# urbanNoiseMonitor.net
KiCad netlist of a schematic drawn in EAGLE
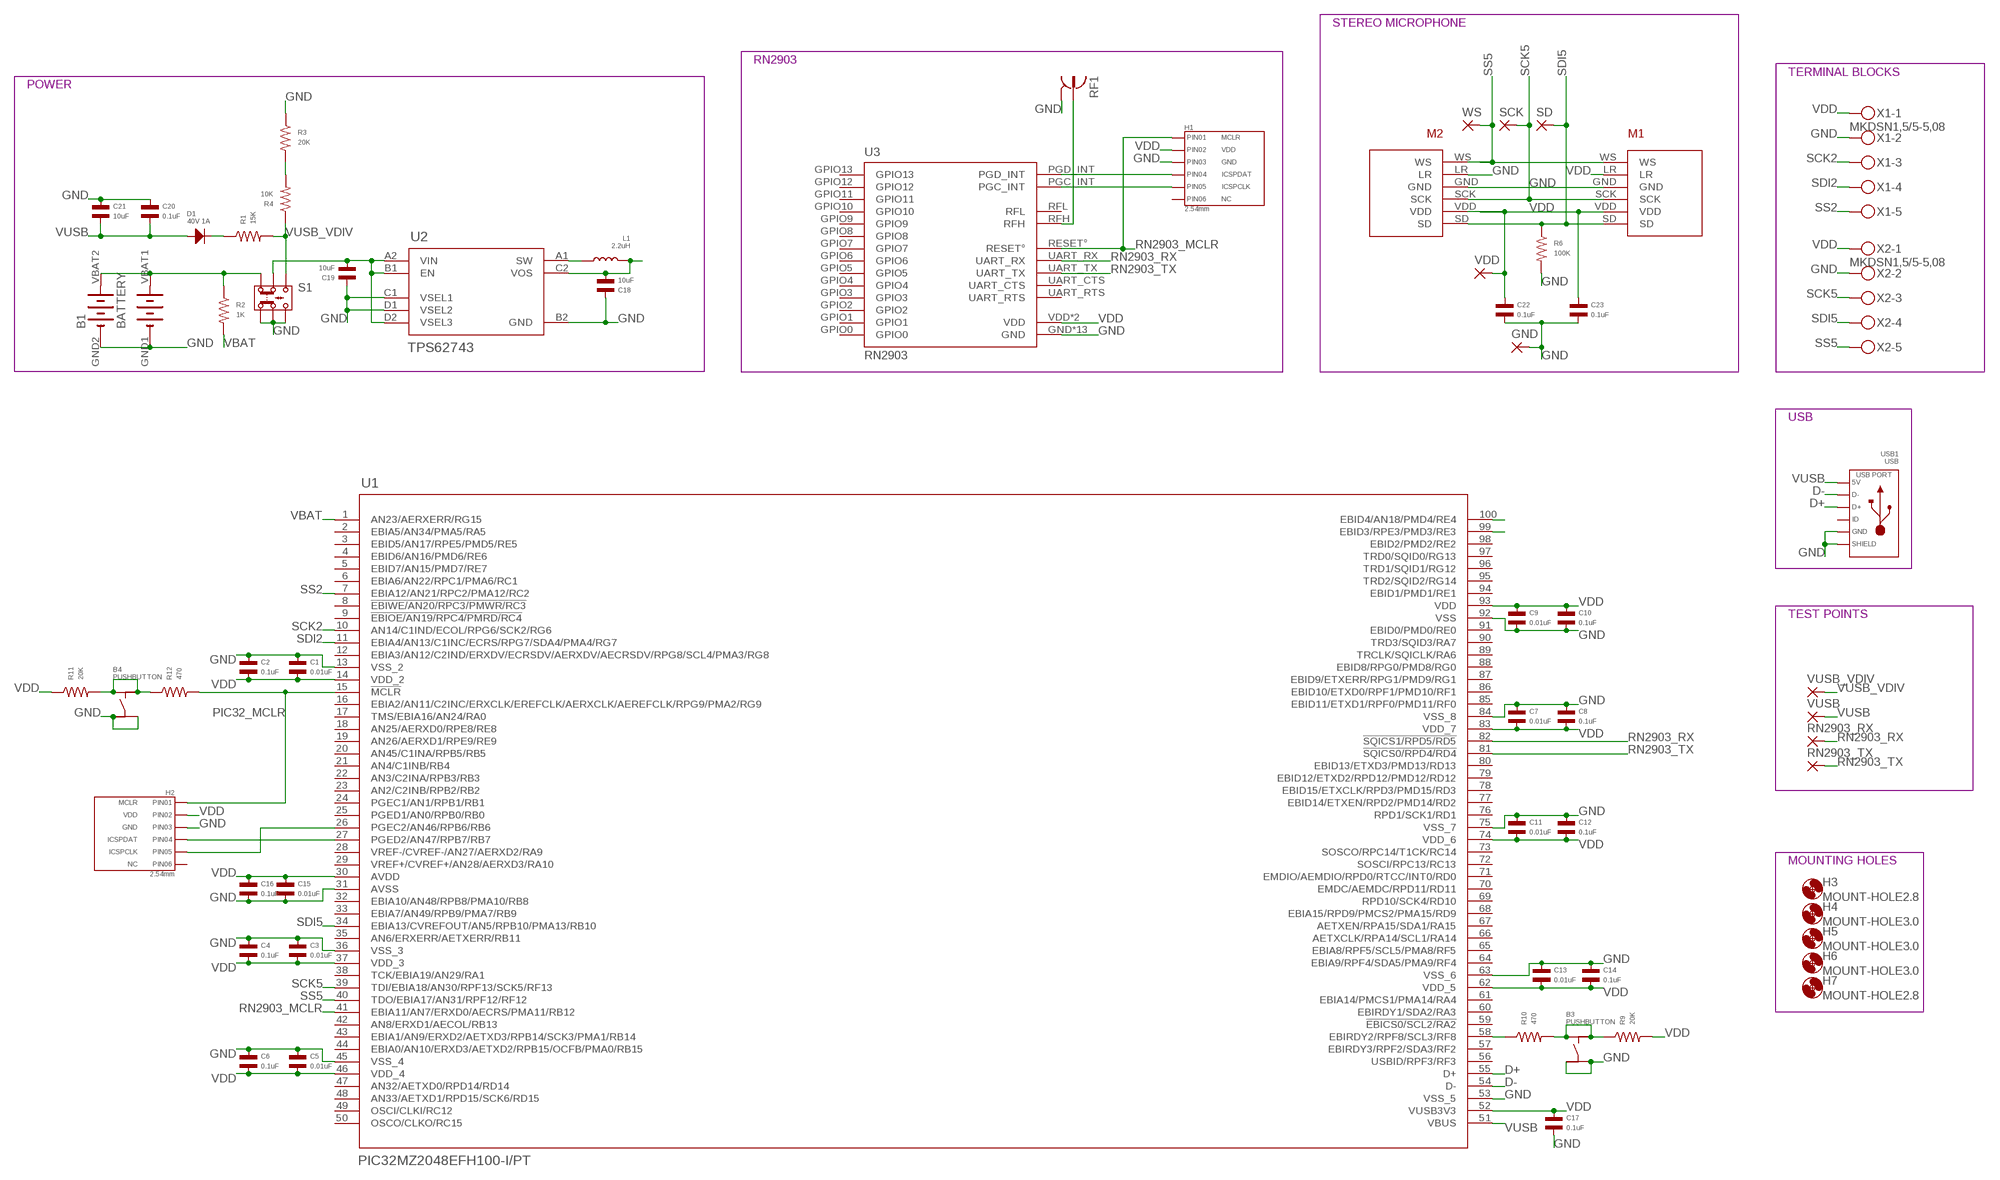
[diagram p0: schematic, sheet 1]

(export (version "E")
  (design (tool "Eeschema 10.0.6"))
  (components
    (comp (ref "B1")
      (value "BATTERY")
      (footprint "eagle-import:36-2227-ND")
      (fields (field (name "MPN") "36-2227-ND"))
      (libsource (lib "eagle-import") (part "BATTERY"))
    )
    (comp (ref "B3")
      (value "PUSHBUTTON")
      (footprint "eagle-import:TACT6MM")
      (fields (field (name "MPN") "MF-SW-TACT-6MM"))
      (libsource (lib "eagle-import") (part "PUSHBUTTON"))
    )
    (comp (ref "B4")
      (value "PUSHBUTTON")
      (footprint "eagle-import:TACT6MM")
      (fields (field (name "MPN") "MF-SW-TACT-6MM"))
      (libsource (lib "eagle-import") (part "PUSHBUTTON"))
    )
    (comp (ref "C1")
      (value "0.01uF")
      (footprint "eagle-import:C0402")
      (fields (field (name "MPN") "MF-CAP-0402-0.01uF"))
      (libsource (lib "eagle-import") (part "CAPACITOR_NP"))
    )
    (comp (ref "C2")
      (value "0.1uF")
      (footprint "eagle-import:C0402")
      (fields (field (name "MPN") "MF-CAP-0402-0.1uF"))
      (libsource (lib "eagle-import") (part "CAPACITOR_NP"))
    )
    (comp (ref "C3")
      (value "0.01uF")
      (footprint "eagle-import:C0402")
      (fields (field (name "MPN") "MF-CAP-0402-0.01uF"))
      (libsource (lib "eagle-import") (part "CAPACITOR_NP"))
    )
    (comp (ref "C4")
      (value "0.1uF")
      (footprint "eagle-import:C0402")
      (fields (field (name "MPN") "MF-CAP-0402-0.1uF"))
      (libsource (lib "eagle-import") (part "CAPACITOR_NP"))
    )
    (comp (ref "C5")
      (value "0.01uF")
      (footprint "eagle-import:C0402")
      (fields (field (name "MPN") "MF-CAP-0402-0.01uF"))
      (libsource (lib "eagle-import") (part "CAPACITOR_NP"))
    )
    (comp (ref "C6")
      (value "0.1uF")
      (footprint "eagle-import:C0402")
      (fields (field (name "MPN") "MF-CAP-0402-0.1uF"))
      (libsource (lib "eagle-import") (part "CAPACITOR_NP"))
    )
    (comp (ref "C7")
      (value "0.01uF")
      (footprint "eagle-import:C0402")
      (fields (field (name "MPN") "MF-CAP-0402-0.01uF"))
      (libsource (lib "eagle-import") (part "CAPACITOR_NP"))
    )
    (comp (ref "C8")
      (value "0.1uF")
      (footprint "eagle-import:C0402")
      (fields (field (name "MPN") "MF-CAP-0402-0.1uF"))
      (libsource (lib "eagle-import") (part "CAPACITOR_NP"))
    )
    (comp (ref "C9")
      (value "0.01uF")
      (footprint "eagle-import:C0402")
      (fields (field (name "MPN") "MF-CAP-0402-0.01uF"))
      (libsource (lib "eagle-import") (part "CAPACITOR_NP"))
    )
    (comp (ref "C10")
      (value "0.1uF")
      (footprint "eagle-import:C0402")
      (fields (field (name "MPN") "MF-CAP-0402-0.1uF"))
      (libsource (lib "eagle-import") (part "CAPACITOR_NP"))
    )
    (comp (ref "C11")
      (value "0.01uF")
      (footprint "eagle-import:C0402")
      (fields (field (name "MPN") "MF-CAP-0402-0.01uF"))
      (libsource (lib "eagle-import") (part "CAPACITOR_NP"))
    )
    (comp (ref "C12")
      (value "0.1uF")
      (footprint "eagle-import:C0402")
      (fields (field (name "MPN") "MF-CAP-0402-0.1uF"))
      (libsource (lib "eagle-import") (part "CAPACITOR_NP"))
    )
    (comp (ref "C13")
      (value "0.01uF")
      (footprint "eagle-import:C0402")
      (fields (field (name "MPN") "MF-CAP-0402-0.01uF"))
      (libsource (lib "eagle-import") (part "CAPACITOR_NP"))
    )
    (comp (ref "C14")
      (value "0.1uF")
      (footprint "eagle-import:C0402")
      (fields (field (name "MPN") "MF-CAP-0402-0.1uF"))
      (libsource (lib "eagle-import") (part "CAPACITOR_NP"))
    )
    (comp (ref "C15")
      (value "0.01uF")
      (footprint "eagle-import:C0402")
      (fields (field (name "MPN") "MF-CAP-0402-0.01uF"))
      (libsource (lib "eagle-import") (part "CAPACITOR_NP"))
    )
    (comp (ref "C16")
      (value "0.1uF")
      (footprint "eagle-import:C0402")
      (fields (field (name "MPN") "MF-CAP-0402-0.1uF"))
      (libsource (lib "eagle-import") (part "CAPACITOR_NP"))
    )
    (comp (ref "C17")
      (value "0.1uF")
      (footprint "eagle-import:C0402")
      (fields (field (name "MPN") "MF-CAP-0402-0.1uF"))
      (libsource (lib "eagle-import") (part "CAPACITOR_NP"))
    )
    (comp (ref "C18")
      (value "10uF")
      (footprint "eagle-import:C1206")
      (fields (field (name "MPN") "MF-CAP-1206-10uF"))
      (libsource (lib "eagle-import") (part "CAPACITOR_NPC1206"))
    )
    (comp (ref "C19")
      (value "10uF")
      (footprint "eagle-import:C1206")
      (fields (field (name "MPN") "MF-CAP-1206-10uF"))
      (libsource (lib "eagle-import") (part "CAPACITOR_NPC1206"))
    )
    (comp (ref "C20")
      (value "0.1uF")
      (footprint "eagle-import:C0402")
      (fields (field (name "MPN") "MF-CAP-0402-0.1uF"))
      (libsource (lib "eagle-import") (part "CAPACITOR_NP"))
    )
    (comp (ref "C21")
      (value "10uF")
      (footprint "eagle-import:C1206")
      (fields (field (name "MPN") "MF-CAP-1206-10uF"))
      (libsource (lib "eagle-import") (part "CAPACITOR_NPC1206"))
    )
    (comp (ref "C22")
      (value "0.1uF")
      (footprint "eagle-import:C0402")
      (fields (field (name "MPN") "MF-CAP-0402-0.1uF"))
      (libsource (lib "eagle-import") (part "CAPACITOR_NP"))
    )
    (comp (ref "C23")
      (value "0.1uF")
      (footprint "eagle-import:C0402")
      (fields (field (name "MPN") "MF-CAP-0402-0.1uF"))
      (libsource (lib "eagle-import") (part "CAPACITOR_NP"))
    )
    (comp (ref "D1")
      (value "40V 1A")
      (footprint "eagle-import:SMA")
      (fields (field (name "MPN") "MF-DIO-SMA-B140"))
      (libsource (lib "eagle-import") (part "SCHOTTKY_DIODE"))
    )
    (comp (ref "GND")
      (value "2,54/1,0")
      (footprint "eagle-import:2,54_1,0")
      (libsource (lib "eagle-import") (part "2,54/1,0"))
    )
    (comp (ref "H1")
      (value "2.54mm")
      (footprint "eagle-import:PTH_2.54MM_01X06")
      (fields
        (field (name "MPN") "MF-CON-2.54mm-01x06")
        (field (name "LABEL01") "MCLR")
        (field (name "LABEL02") "VDD")
        (field (name "LABEL03") "GND")
        (field (name "LABEL04") "ICSPDAT")
        (field (name "LABEL05") "ICSPCLK")
        (field (name "LABEL06") "NC")
        (field (name "POPULATE") "0")
      )
      (libsource (lib "eagle-import") (part "HEADER_PINS"))
    )
    (comp (ref "H2")
      (value "2.54mm")
      (footprint "eagle-import:PTH_2.54MM_01X06")
      (fields
        (field (name "MPN") "MF-CON-2.54mm-01x06")
        (field (name "LABEL01") "MCLR")
        (field (name "LABEL02") "VDD")
        (field (name "LABEL03") "GND")
        (field (name "LABEL04") "ICSPDAT")
        (field (name "LABEL05") "ICSPCLK")
        (field (name "LABEL06") "NC")
        (field (name "POPULATE") "0")
      )
      (libsource (lib "eagle-import") (part "HEADER_PINS"))
    )
    (comp (ref "H3")
      (value "MOUNT-HOLE2.8")
      (footprint "eagle-import:2,8")
      (libsource (lib "eagle-import") (part "MOUNT-HOLE2.8"))
    )
    (comp (ref "H4")
      (value "MOUNT-HOLE3.0")
      (footprint "eagle-import:3,0")
      (libsource (lib "eagle-import") (part "MOUNT-HOLE3.0"))
    )
    (comp (ref "H5")
      (value "MOUNT-HOLE3.0")
      (footprint "eagle-import:3,0")
      (libsource (lib "eagle-import") (part "MOUNT-HOLE3.0"))
    )
    (comp (ref "H6")
      (value "MOUNT-HOLE3.0")
      (footprint "eagle-import:3,0")
      (libsource (lib "eagle-import") (part "MOUNT-HOLE3.0"))
    )
    (comp (ref "H7")
      (value "MOUNT-HOLE2.8")
      (footprint "eagle-import:2,8")
      (libsource (lib "eagle-import") (part "MOUNT-HOLE2.8"))
    )
    (comp (ref "L1")
      (value "2.2uH")
      (footprint "eagle-import:L2016")
      (fields (field (name "MPN") "1285AS-H-2R2M=P2"))
      (libsource (lib "eagle-import") (part "DFE201610C"))
    )
    (comp (ref "M1")
      (value "MICROPHONE")
      (footprint "eagle-import:ICS-43434")
      (fields (field (name "MPN") "ICS-43434"))
      (libsource (lib "eagle-import") (part "MICROPHONE"))
    )
    (comp (ref "M2")
      (value "MICROPHONE")
      (footprint "eagle-import:ICS-43434")
      (fields (field (name "MPN") "ICS-43434"))
      (libsource (lib "eagle-import") (part "MICROPHONE"))
    )
    (comp (ref "R1")
      (value "15K")
      (footprint "eagle-import:R0402")
      (fields (field (name "MPN") "MF-RES-0402-15K"))
      (libsource (lib "eagle-import") (part "RESISTOR"))
    )
    (comp (ref "R2")
      (value "1K")
      (footprint "eagle-import:R0402")
      (fields (field (name "MPN") "MF-RES-0402-1K"))
      (libsource (lib "eagle-import") (part "RESISTOR"))
    )
    (comp (ref "R3")
      (value "20K")
      (footprint "eagle-import:R0805")
      (fields (field (name "MPN") "MF-RES-0805-20K"))
      (libsource (lib "eagle-import") (part "RESISTORR0805"))
    )
    (comp (ref "R4")
      (value "10K")
      (footprint "eagle-import:R0402")
      (fields (field (name "MPN") "MF-RES-0402-10K"))
      (libsource (lib "eagle-import") (part "RESISTOR"))
    )
    (comp (ref "R6")
      (value "100K")
      (footprint "eagle-import:R0402")
      (fields (field (name "MPN") "MF-RES-0402-100K"))
      (libsource (lib "eagle-import") (part "RESISTOR"))
    )
    (comp (ref "R9")
      (value "20K")
      (footprint "eagle-import:R0805")
      (fields (field (name "MPN") "MF-RES-0805-20K"))
      (libsource (lib "eagle-import") (part "RESISTORR0805"))
    )
    (comp (ref "R10")
      (value "470")
      (footprint "eagle-import:R0402")
      (fields (field (name "MPN") "MF-RES-0402-470"))
      (libsource (lib "eagle-import") (part "RESISTOR"))
    )
    (comp (ref "R11")
      (value "20K")
      (footprint "eagle-import:R0805")
      (fields (field (name "MPN") "MF-RES-0805-20K"))
      (libsource (lib "eagle-import") (part "RESISTORR0805"))
    )
    (comp (ref "R12")
      (value "470")
      (footprint "eagle-import:R0402")
      (fields (field (name "MPN") "MF-RES-0402-470"))
      (libsource (lib "eagle-import") (part "RESISTOR"))
    )
    (comp (ref "RF1")
      (value "SMA_JACK")
      (footprint "eagle-import:J502-ND-142-0711-821_826")
      (fields (field (name "MPN") "SMA-J-P-H-ST-EM1"))
      (libsource (lib "eagle-import") (part "SMA_JACK"))
    )
    (comp (ref "RN2903_RX")
      (value "2,54/1,0")
      (footprint "eagle-import:2,54_1,0")
      (libsource (lib "eagle-import") (part "2,54/1,0"))
    )
    (comp (ref "RN2903_TX")
      (value "2,54/1,0")
      (footprint "eagle-import:2,54_1,0")
      (libsource (lib "eagle-import") (part "2,54/1,0"))
    )
    (comp (ref "S1")
      (value "SLIDING_SWITCH")
      (footprint "eagle-import:DPDT")
      (fields (field (name "MPN") "JS202011SCQN"))
      (libsource (lib "eagle-import") (part "SLIDING_SWITCH"))
    )
    (comp (ref "SCK")
      (value "2,54/1,0")
      (footprint "eagle-import:2,54_1,0")
      (libsource (lib "eagle-import") (part "2,54/1,0"))
    )
    (comp (ref "SD")
      (value "2,54/1,0")
      (footprint "eagle-import:2,54_1,0")
      (libsource (lib "eagle-import") (part "2,54/1,0"))
    )
    (comp (ref "U1")
      (value "PIC32MZ2048EFH100-I/PT")
      (footprint "eagle-import:TQFP100_12X12MC")
      (libsource (lib "eagle-import") (part "PIC32MZ2048EFH100-I/PT"))
    )
    (comp (ref "U2")
      (value "TPS62743")
      (footprint "eagle-import:YFP0008AGAC")
      (fields (field (name "MPN") "TPS62743YFPR"))
      (libsource (lib "eagle-import") (part "TPS62743"))
    )
    (comp (ref "U3")
      (value "RN2903")
      (footprint "eagle-import:RN2903")
      (fields (field (name "MPN") "RN2903A-I/RM098"))
      (libsource (lib "eagle-import") (part "RN2903"))
    )
    (comp (ref "USB1")
      (value "USB")
      (footprint "eagle-import:MICROUSB-RIGHT")
      (fields (field (name "MPN") "MF-CON-MICROUSB-RIGHT"))
      (libsource (lib "eagle-import") (part "USB"))
    )
    (comp (ref "VDD")
      (value "2,54/1,0")
      (footprint "eagle-import:2,54_1,0")
      (libsource (lib "eagle-import") (part "2,54/1,0"))
    )
    (comp (ref "VUSB")
      (value "2,54/1,0")
      (footprint "eagle-import:2,54_1,0")
      (libsource (lib "eagle-import") (part "2,54/1,0"))
    )
    (comp (ref "VUSB_VDIV")
      (value "2,54/1,0")
      (footprint "eagle-import:2,54_1,0")
      (libsource (lib "eagle-import") (part "2,54/1,0"))
    )
    (comp (ref "WS")
      (value "2,54/1,0")
      (footprint "eagle-import:2,54_1,0")
      (libsource (lib "eagle-import") (part "2,54/1,0"))
    )
    (comp (ref "X1")
      (value "MKDSN1,5/5-5,08")
      (footprint "eagle-import:MKDSN1,5_5-5,08")
      (fields (field (name "MPN") "1729157") (field (name "POPULATE") "0"))
      (libsource (lib "eagle-import") (part "MKDSN1,5/5-5,08"))
    )
    (comp (ref "X2")
      (value "MKDSN1,5/5-5,08")
      (footprint "eagle-import:MKDSN1,5_5-5,08")
      (fields (field (name "MPN") "1729157") (field (name "POPULATE") "0"))
      (libsource (lib "eagle-import") (part "MKDSN1,5/5-5,08"))
    )
  )
  (nets
    (net (code "1") (name "/D+") (class "Default")
      (node (ref "U1") (pin "55") (pinfunction "D+_55") (pintype "passive"))
      (node (ref "USB1") (pin "3") (pinfunction "D+_3") (pintype "bidirectional"))
    )
    (net (code "2") (name "/D-") (class "Default")
      (node (ref "U1") (pin "54") (pinfunction "D-_54") (pintype "passive"))
      (node (ref "USB1") (pin "2") (pinfunction "D-_2") (pintype "bidirectional"))
    )
    (net (code "3") (name "/GND") (class "Default")
      (node (ref "B1") (pin "GND1") (pinfunction "GND1_GND1") (pintype "passive"))
      (node (ref "B1") (pin "GND2") (pinfunction "GND2_GND2") (pintype "passive"))
      (node (ref "B3") (pin "P$3") (pinfunction "P$3_P$3") (pintype "bidirectional"))
      (node (ref "B3") (pin "P$4") (pinfunction "P$4_P$4") (pintype "bidirectional"))
      (node (ref "B4") (pin "P$3") (pinfunction "P$3_P$3") (pintype "bidirectional"))
      (node (ref "B4") (pin "P$4") (pinfunction "P$4_P$4") (pintype "bidirectional"))
      (node (ref "C1") (pin "P$1") (pinfunction "P$1_P$1") (pintype "passive"))
      (node (ref "C10") (pin "P$2") (pinfunction "P$2_P$2") (pintype "passive"))
      (node (ref "C11") (pin "P$1") (pinfunction "P$1_P$1") (pintype "passive"))
      (node (ref "C12") (pin "P$1") (pinfunction "P$1_P$1") (pintype "passive"))
      (node (ref "C13") (pin "P$1") (pinfunction "P$1_P$1") (pintype "passive"))
      (node (ref "C14") (pin "P$1") (pinfunction "P$1_P$1") (pintype "passive"))
      (node (ref "C15") (pin "P$2") (pinfunction "P$2_P$2") (pintype "passive"))
      (node (ref "C16") (pin "P$2") (pinfunction "P$2_P$2") (pintype "passive"))
      (node (ref "C17") (pin "P$2") (pinfunction "P$2_P$2") (pintype "passive"))
      (node (ref "C18") (pin "P$1") (pinfunction "P$1_P$1") (pintype "passive"))
      (node (ref "C19") (pin "P$1") (pinfunction "P$1_P$1") (pintype "passive"))
      (node (ref "C2") (pin "P$1") (pinfunction "P$1_P$1") (pintype "passive"))
      (node (ref "C20") (pin "P$1") (pinfunction "P$1_P$1") (pintype "passive"))
      (node (ref "C21") (pin "P$1") (pinfunction "P$1_P$1") (pintype "passive"))
      (node (ref "C22") (pin "P$2") (pinfunction "P$2_P$2") (pintype "passive"))
      (node (ref "C23") (pin "P$2") (pinfunction "P$2_P$2") (pintype "passive"))
      (node (ref "C3") (pin "P$1") (pinfunction "P$1_P$1") (pintype "passive"))
      (node (ref "C4") (pin "P$1") (pinfunction "P$1_P$1") (pintype "passive"))
      (node (ref "C5") (pin "P$1") (pinfunction "P$1_P$1") (pintype "passive"))
      (node (ref "C6") (pin "P$1") (pinfunction "P$1_P$1") (pintype "passive"))
      (node (ref "C7") (pin "P$1") (pinfunction "P$1_P$1") (pintype "passive"))
      (node (ref "C8") (pin "P$1") (pinfunction "P$1_P$1") (pintype "passive"))
      (node (ref "C9") (pin "P$2") (pinfunction "P$2_P$2") (pintype "passive"))
      (node (ref "GND") (pin "1") (pinfunction "P_1") (pintype "passive"))
      (node (ref "H1") (pin "P$3") (pinfunction "PIN3_P$3") (pintype "bidirectional"))
      (node (ref "H2") (pin "P$3") (pinfunction "PIN3_P$3") (pintype "bidirectional"))
      (node (ref "M1") (pin "GND") (pinfunction "GND_GND") (pintype "bidirectional"))
      (node (ref "M2") (pin "GND") (pinfunction "GND_GND") (pintype "bidirectional"))
      (node (ref "M2") (pin "LR") (pinfunction "LR_LR") (pintype "bidirectional"))
      (node (ref "R3") (pin "P$1") (pinfunction "P$1_P$1") (pintype "passive"))
      (node (ref "R6") (pin "P$2") (pinfunction "P$2_P$2") (pintype "passive"))
      (node (ref "RF1") (pin "G@1") (pinfunction "2_G@1") (pintype "passive"))
      (node (ref "RF1") (pin "G@2") (pinfunction "2_G@2") (pintype "passive"))
      (node (ref "RF1") (pin "G@3") (pinfunction "2_G@3") (pintype "passive"))
      (node (ref "RF1") (pin "G@4") (pinfunction "2_G@4") (pintype "passive"))
      (node (ref "S1") (pin "1") (pinfunction "1_1") (pintype "passive"))
      (node (ref "S1") (pin "2") (pinfunction "2_2") (pintype "passive"))
      (node (ref "S1") (pin "3") (pinfunction "3_3") (pintype "passive"))
      (node (ref "U1") (pin "13") (pinfunction "VSS_2_13") (pintype "power_in"))
      (node (ref "U1") (pin "31") (pinfunction "AVSS_31") (pintype "power_in"))
      (node (ref "U1") (pin "36") (pinfunction "VSS_3_36") (pintype "power_in"))
      (node (ref "U1") (pin "45") (pinfunction "VSS_4_45") (pintype "power_in"))
      (node (ref "U1") (pin "53") (pinfunction "VSS_5_53") (pintype "power_in"))
      (node (ref "U1") (pin "63") (pinfunction "VSS_6_63") (pintype "power_in"))
      (node (ref "U1") (pin "75") (pinfunction "VSS_7_75") (pintype "power_in"))
      (node (ref "U1") (pin "84") (pinfunction "VSS_8_84") (pintype "power_in"))
      (node (ref "U1") (pin "92") (pinfunction "VSS_92") (pintype "power_in"))
      (node (ref "U2") (pin "B2") (pinfunction "GND_B2") (pintype "power_in"))
      (node (ref "U2") (pin "C1") (pinfunction "VSEL1_C1") (pintype "input"))
      (node (ref "U2") (pin "D1") (pinfunction "VSEL2_D1") (pintype "input"))
      (node (ref "U3") (pin "GND") (pinfunction "GND_GND") (pintype "bidirectional"))
      (node (ref "U3") (pin "GND1") (pinfunction "GND_GND1") (pintype "bidirectional"))
      (node (ref "U3") (pin "GND10") (pinfunction "GND_GND10") (pintype "bidirectional"))
      (node (ref "U3") (pin "GND11") (pinfunction "GND_GND11") (pintype "bidirectional"))
      (node (ref "U3") (pin "GND12") (pinfunction "GND_GND12") (pintype "bidirectional"))
      (node (ref "U3") (pin "GND2") (pinfunction "GND_GND2") (pintype "bidirectional"))
      (node (ref "U3") (pin "GND3") (pinfunction "GND_GND3") (pintype "bidirectional"))
      (node (ref "U3") (pin "GND4") (pinfunction "GND_GND4") (pintype "bidirectional"))
      (node (ref "U3") (pin "GND5") (pinfunction "GND_GND5") (pintype "bidirectional"))
      (node (ref "U3") (pin "GND6") (pinfunction "GND_GND6") (pintype "bidirectional"))
      (node (ref "U3") (pin "GND7") (pinfunction "GND_GND7") (pintype "bidirectional"))
      (node (ref "U3") (pin "GND8") (pinfunction "GND_GND8") (pintype "bidirectional"))
      (node (ref "U3") (pin "GND9") (pinfunction "GND_GND9") (pintype "bidirectional"))
      (node (ref "USB1") (pin "5") (pinfunction "GND_5") (pintype "power_in"))
      (node (ref "USB1") (pin "S1") (pinfunction "SLD_S1") (pintype "power_in"))
      (node (ref "USB1") (pin "S2") (pinfunction "SLD_S2") (pintype "power_in"))
      (node (ref "USB1") (pin "S3") (pinfunction "SLD_S3") (pintype "power_in"))
      (node (ref "USB1") (pin "S4") (pinfunction "SLD_S4") (pintype "power_in"))
      (node (ref "USB1") (pin "S5") (pinfunction "SLD_S5") (pintype "power_in"))
      (node (ref "USB1") (pin "S6") (pinfunction "SLD_S6") (pintype "power_in"))
      (node (ref "X1") (pin "2") (pinfunction "KL_2") (pintype "passive"))
      (node (ref "X2") (pin "2") (pinfunction "KL_2") (pintype "passive"))
    )
    (net (code "4") (name "/PIC32_MCLR") (class "Default")
      (node (ref "H2") (pin "P$1") (pinfunction "PIN1_P$1") (pintype "bidirectional"))
      (node (ref "R12") (pin "P$2") (pinfunction "P$2_P$2") (pintype "passive"))
      (node (ref "U1") (pin "15") (pinfunction "~{MCLR}_15") (pintype "passive"))
    )
    (net (code "5") (name "/RN2903_MCLR") (class "Default")
      (node (ref "H1") (pin "P$1") (pinfunction "PIN1_P$1") (pintype "bidirectional"))
      (node (ref "U1") (pin "41") (pinfunction "EBIA11/AN7/ERXD0/AECRS/PMA11/RB12_41") (pintype "bidirectional"))
      (node (ref "U3") (pin "RESET°") (pinfunction "RESET°_RESET°") (pintype "bidirectional"))
    )
    (net (code "6") (name "/RN2903_RX") (class "Default")
      (node (ref "RN2903_RX") (pin "1") (pinfunction "P_1") (pintype "passive"))
      (node (ref "U1") (pin "82") (pinfunction "~{SQICS1/RPD5/RD5}_82") (pintype "bidirectional"))
      (node (ref "U3") (pin "UART_RX") (pinfunction "UART_RX_UART_RX") (pintype "bidirectional"))
    )
    (net (code "7") (name "/RN2903_TX") (class "Default")
      (node (ref "RN2903_TX") (pin "1") (pinfunction "P_1") (pintype "passive"))
      (node (ref "U1") (pin "81") (pinfunction "~{SQICS0/RPD4/RD4}_81") (pintype "bidirectional"))
      (node (ref "U3") (pin "UART_TX") (pinfunction "UART_TX_UART_TX") (pintype "bidirectional"))
    )
    (net (code "8") (name "/SCK2") (class "Default")
      (node (ref "U1") (pin "10") (pinfunction "AN14/C1IND/ECOL/RPG6/SCK2/RG6_10") (pintype "bidirectional"))
      (node (ref "X1") (pin "3") (pinfunction "KL_3") (pintype "passive"))
    )
    (net (code "9") (name "/SCK5") (class "Default")
      (node (ref "M1") (pin "SCK") (pinfunction "SCK_SCK") (pintype "bidirectional"))
      (node (ref "M2") (pin "SCK") (pinfunction "SCK_SCK") (pintype "bidirectional"))
      (node (ref "SCK") (pin "1") (pinfunction "P_1") (pintype "passive"))
      (node (ref "U1") (pin "39") (pinfunction "TDI/EBIA18/AN30/RPF13/SCK5/RF13_39") (pintype "bidirectional"))
      (node (ref "X2") (pin "3") (pinfunction "KL_3") (pintype "passive"))
    )
    (net (code "10") (name "/SDI2") (class "Default")
      (node (ref "U1") (pin "11") (pinfunction "EBIA4/AN13/C1INC/ECRS/RPG7/SDA4/PMA4/RG7_11") (pintype "bidirectional"))
      (node (ref "X1") (pin "4") (pinfunction "KL_4") (pintype "passive"))
    )
    (net (code "11") (name "/SDI5") (class "Default")
      (node (ref "M1") (pin "SD") (pinfunction "SD_SD") (pintype "bidirectional"))
      (node (ref "M2") (pin "SD") (pinfunction "SD_SD") (pintype "bidirectional"))
      (node (ref "R6") (pin "P$1") (pinfunction "P$1_P$1") (pintype "passive"))
      (node (ref "SD") (pin "1") (pinfunction "P_1") (pintype "passive"))
      (node (ref "U1") (pin "34") (pinfunction "EBIA13/CVREFOUT/AN5/RPB10/PMA13/RB10_34") (pintype "bidirectional"))
      (node (ref "X2") (pin "4") (pinfunction "KL_4") (pintype "passive"))
    )
    (net (code "12") (name "/SS2") (class "Default")
      (node (ref "U1") (pin "7") (pinfunction "EBIA12/AN21/RPC2/PMA12/RC2_7") (pintype "bidirectional"))
      (node (ref "X1") (pin "5") (pinfunction "KL_5") (pintype "passive"))
    )
    (net (code "13") (name "/SS5") (class "Default")
      (node (ref "M1") (pin "WS") (pinfunction "WS_WS") (pintype "bidirectional"))
      (node (ref "M2") (pin "WS") (pinfunction "WS_WS") (pintype "bidirectional"))
      (node (ref "U1") (pin "40") (pinfunction "TDO/EBIA17/AN31/RPF12/RF12_40") (pintype "bidirectional"))
      (node (ref "WS") (pin "1") (pinfunction "P_1") (pintype "passive"))
      (node (ref "X2") (pin "5") (pinfunction "KL_5") (pintype "passive"))
    )
    (net (code "14") (name "/VBAT") (class "Default")
      (node (ref "R2") (pin "P$2") (pinfunction "P$2_P$2") (pintype "passive"))
      (node (ref "U1") (pin "1") (pinfunction "AN23/AERXERR/RG15_1") (pintype "bidirectional"))
    )
    (net (code "15") (name "/VDD") (class "Default")
      (node (ref "C1") (pin "P$2") (pinfunction "P$2_P$2") (pintype "passive"))
      (node (ref "C10") (pin "P$1") (pinfunction "P$1_P$1") (pintype "passive"))
      (node (ref "C11") (pin "P$2") (pinfunction "P$2_P$2") (pintype "passive"))
      (node (ref "C12") (pin "P$2") (pinfunction "P$2_P$2") (pintype "passive"))
      (node (ref "C13") (pin "P$2") (pinfunction "P$2_P$2") (pintype "passive"))
      (node (ref "C14") (pin "P$2") (pinfunction "P$2_P$2") (pintype "passive"))
      (node (ref "C15") (pin "P$1") (pinfunction "P$1_P$1") (pintype "passive"))
      (node (ref "C16") (pin "P$1") (pinfunction "P$1_P$1") (pintype "passive"))
      (node (ref "C17") (pin "P$1") (pinfunction "P$1_P$1") (pintype "passive"))
      (node (ref "C18") (pin "P$2") (pinfunction "P$2_P$2") (pintype "passive"))
      (node (ref "C2") (pin "P$2") (pinfunction "P$2_P$2") (pintype "passive"))
      (node (ref "C22") (pin "P$1") (pinfunction "P$1_P$1") (pintype "passive"))
      (node (ref "C23") (pin "P$1") (pinfunction "P$1_P$1") (pintype "passive"))
      (node (ref "C3") (pin "P$2") (pinfunction "P$2_P$2") (pintype "passive"))
      (node (ref "C4") (pin "P$2") (pinfunction "P$2_P$2") (pintype "passive"))
      (node (ref "C5") (pin "P$2") (pinfunction "P$2_P$2") (pintype "passive"))
      (node (ref "C6") (pin "P$2") (pinfunction "P$2_P$2") (pintype "passive"))
      (node (ref "C7") (pin "P$2") (pinfunction "P$2_P$2") (pintype "passive"))
      (node (ref "C8") (pin "P$2") (pinfunction "P$2_P$2") (pintype "passive"))
      (node (ref "C9") (pin "P$1") (pinfunction "P$1_P$1") (pintype "passive"))
      (node (ref "H1") (pin "P$2") (pinfunction "PIN2_P$2") (pintype "bidirectional"))
      (node (ref "H2") (pin "P$2") (pinfunction "PIN2_P$2") (pintype "bidirectional"))
      (node (ref "L1") (pin "P$1") (pinfunction "P$1_P$1") (pintype "passive"))
      (node (ref "M1") (pin "LR") (pinfunction "LR_LR") (pintype "bidirectional"))
      (node (ref "M1") (pin "VDD") (pinfunction "VDD_VDD") (pintype "bidirectional"))
      (node (ref "M2") (pin "VDD") (pinfunction "VDD_VDD") (pintype "bidirectional"))
      (node (ref "R11") (pin "P$1") (pinfunction "P$1_P$1") (pintype "passive"))
      (node (ref "R9") (pin "P$2") (pinfunction "P$2_P$2") (pintype "passive"))
      (node (ref "U1") (pin "14") (pinfunction "VDD_2_14") (pintype "power_in"))
      (node (ref "U1") (pin "30") (pinfunction "AVDD_30") (pintype "power_in"))
      (node (ref "U1") (pin "37") (pinfunction "VDD_3_37") (pintype "power_in"))
      (node (ref "U1") (pin "46") (pinfunction "VDD_4_46") (pintype "power_in"))
      (node (ref "U1") (pin "52") (pinfunction "VUSB3V3_52") (pintype "power_in"))
      (node (ref "U1") (pin "62") (pinfunction "VDD_5_62") (pintype "power_in"))
      (node (ref "U1") (pin "74") (pinfunction "VDD_6_74") (pintype "power_in"))
      (node (ref "U1") (pin "83") (pinfunction "VDD_7_83") (pintype "power_in"))
      (node (ref "U1") (pin "93") (pinfunction "VDD_93") (pintype "power_in"))
      (node (ref "U2") (pin "C2") (pinfunction "VOS_C2") (pintype "input"))
      (node (ref "U3") (pin "VDD") (pinfunction "VDD_VDD") (pintype "bidirectional"))
      (node (ref "U3") (pin "VDD2") (pinfunction "VDD_VDD2") (pintype "bidirectional"))
      (node (ref "VDD") (pin "1") (pinfunction "P_1") (pintype "passive"))
      (node (ref "X1") (pin "1") (pinfunction "KL_1") (pintype "passive"))
      (node (ref "X2") (pin "1") (pinfunction "KL_1") (pintype "passive"))
    )
    (net (code "16") (name "/VUSB") (class "Default")
      (node (ref "C20") (pin "P$2") (pinfunction "P$2_P$2") (pintype "passive"))
      (node (ref "C21") (pin "P$2") (pinfunction "P$2_P$2") (pintype "passive"))
      (node (ref "D1") (pin "ANODE") (pinfunction "ANODE_ANODE") (pintype "bidirectional"))
      (node (ref "U1") (pin "51") (pinfunction "VBUS_51") (pintype "power_in"))
      (node (ref "USB1") (pin "1") (pinfunction "5V_1") (pintype "power_in"))
      (node (ref "VUSB") (pin "1") (pinfunction "P_1") (pintype "passive"))
    )
    (net (code "17") (name "/VUSB_VDIV") (class "Default")
      (node (ref "R1") (pin "P$2") (pinfunction "P$2_P$2") (pintype "passive"))
      (node (ref "R4") (pin "P$1") (pinfunction "P$1_P$1") (pintype "passive"))
      (node (ref "S1") (pin "6") (pinfunction "6_6") (pintype "passive"))
      (node (ref "VUSB_VDIV") (pin "1") (pinfunction "P_1") (pintype "passive"))
    )
    (net (code "18") (name "Net-(B1-PadVBAT1)") (class "Default")
      (node (ref "B1") (pin "VBAT1") (pinfunction "VBAT1_VBAT1") (pintype "passive"))
      (node (ref "B1") (pin "VBAT2") (pinfunction "VBAT2_VBAT2") (pintype "passive"))
      (node (ref "R2") (pin "P$1") (pinfunction "P$1_P$1") (pintype "passive"))
      (node (ref "S1") (pin "4") (pinfunction "4_4") (pintype "passive"))
    )
    (net (code "19") (name "Net-(B3-PadP$1)") (class "Default")
      (node (ref "B3") (pin "P$1") (pinfunction "P$1_P$1") (pintype "bidirectional"))
      (node (ref "B3") (pin "P$2") (pinfunction "P$2_P$2") (pintype "bidirectional"))
      (node (ref "R10") (pin "P$2") (pinfunction "P$2_P$2") (pintype "passive"))
      (node (ref "R9") (pin "P$1") (pinfunction "P$1_P$1") (pintype "passive"))
    )
    (net (code "20") (name "Net-(B4-PadP$1)") (class "Default")
      (node (ref "B4") (pin "P$1") (pinfunction "P$1_P$1") (pintype "bidirectional"))
      (node (ref "B4") (pin "P$2") (pinfunction "P$2_P$2") (pintype "bidirectional"))
      (node (ref "R11") (pin "P$2") (pinfunction "P$2_P$2") (pintype "passive"))
      (node (ref "R12") (pin "P$1") (pinfunction "P$1_P$1") (pintype "passive"))
    )
    (net (code "21") (name "Net-(D1-PadCATHODE)") (class "Default")
      (node (ref "D1") (pin "CATHODE") (pinfunction "CATHODE_CATHODE") (pintype "bidirectional"))
      (node (ref "R1") (pin "P$1") (pinfunction "P$1_P$1") (pintype "passive"))
    )
    (net (code "22") (name "Net-(H1-PIN4)") (class "Default")
      (node (ref "H1") (pin "P$4") (pinfunction "PIN4_P$4") (pintype "bidirectional"))
      (node (ref "U3") (pin "PGD_INT") (pinfunction "PGD_INT_PGD_INT") (pintype "bidirectional"))
    )
    (net (code "23") (name "Net-(H1-PIN5)") (class "Default")
      (node (ref "H1") (pin "P$5") (pinfunction "PIN5_P$5") (pintype "bidirectional"))
      (node (ref "U3") (pin "PGC_INT") (pinfunction "PGC_INT_PGC_INT") (pintype "bidirectional"))
    )
    (net (code "24") (name "Net-(H2-PIN4)") (class "Default")
      (node (ref "H2") (pin "P$4") (pinfunction "PIN4_P$4") (pintype "bidirectional"))
      (node (ref "U1") (pin "27") (pinfunction "PGED2/AN47/RPB7/RB7_27") (pintype "bidirectional"))
    )
    (net (code "25") (name "Net-(H2-PIN5)") (class "Default")
      (node (ref "H2") (pin "P$5") (pinfunction "PIN5_P$5") (pintype "bidirectional"))
      (node (ref "U1") (pin "26") (pinfunction "PGEC2/AN46/RPB6/RB6_26") (pintype "bidirectional"))
    )
    (net (code "26") (name "Net-(R3-PadP$2)") (class "Default")
      (node (ref "R3") (pin "P$2") (pinfunction "P$2_P$2") (pintype "passive"))
      (node (ref "R4") (pin "P$2") (pinfunction "P$2_P$2") (pintype "passive"))
    )
    (net (code "27") (name "Net-(RF1-Pad1)") (class "Default")
      (node (ref "RF1") (pin "1") (pinfunction "1_1") (pintype "passive"))
      (node (ref "U3") (pin "RFH") (pinfunction "RFH_RFH") (pintype "bidirectional"))
    )
    (net (code "28") (name "Net-(U1-EBIRDY2{slash}RPF8{slash}SCL3{slash}RF8)") (class "Default")
      (node (ref "R10") (pin "P$1") (pinfunction "P$1_P$1") (pintype "passive"))
      (node (ref "U1") (pin "58") (pinfunction "EBIRDY2/RPF8/SCL3/RF8_58") (pintype "bidirectional"))
    )
    (net (code "29") (name "Net-(U2-EN)") (class "Default")
      (node (ref "C19") (pin "P$2") (pinfunction "P$2_P$2") (pintype "passive"))
      (node (ref "S1") (pin "5") (pinfunction "5_5") (pintype "passive"))
      (node (ref "U2") (pin "A2") (pinfunction "VIN_A2") (pintype "power_in"))
      (node (ref "U2") (pin "B1") (pinfunction "EN_B1") (pintype "input"))
      (node (ref "U2") (pin "D2") (pinfunction "VSEL3_D2") (pintype "input"))
    )
    (net (code "30") (name "Net-(U2-SW)") (class "Default")
      (node (ref "L1") (pin "P$2") (pinfunction "P$2_P$2") (pintype "passive"))
      (node (ref "U2") (pin "A1") (pinfunction "SW_A1") (pintype "power_in"))
    )
    (net (code "31") (name "unconnected-(H1-PIN6-PadP$6)") (class "Default")
      (node (ref "H1") (pin "P$6") (pinfunction "PIN6_P$6") (pintype "bidirectional"))
    )
    (net (code "32") (name "unconnected-(H2-PIN6-PadP$6)") (class "Default")
      (node (ref "H2") (pin "P$6") (pinfunction "PIN6_P$6") (pintype "bidirectional"))
    )
    (net (code "33") (name "unconnected-(U1-AETXCLK{slash}RPA14{slash}SCL1{slash}RA14-Pad66)") (class "Default")
      (node (ref "U1") (pin "66") (pinfunction "AETXCLK/RPA14/SCL1/RA14_66") (pintype "bidirectional"))
    )
    (net (code "34") (name "unconnected-(U1-AETXEN{slash}RPA15{slash}SDA1{slash}RA15-Pad67)") (class "Default")
      (node (ref "U1") (pin "67") (pinfunction "AETXEN/RPA15/SDA1/RA15_67") (pintype "bidirectional"))
    )
    (net (code "35") (name "unconnected-(U1-AN2{slash}C2INB{slash}RPB2{slash}RB2-Pad23)") (class "Default")
      (node (ref "U1") (pin "23") (pinfunction "AN2/C2INB/RPB2/RB2_23") (pintype "bidirectional"))
    )
    (net (code "36") (name "unconnected-(U1-AN3{slash}C2INA{slash}RPB3{slash}RB3-Pad22)") (class "Default")
      (node (ref "U1") (pin "22") (pinfunction "AN3/C2INA/RPB3/RB3_22") (pintype "bidirectional"))
    )
    (net (code "37") (name "unconnected-(U1-AN4{slash}C1INB{slash}RB4-Pad21)") (class "Default")
      (node (ref "U1") (pin "21") (pinfunction "AN4/C1INB/RB4_21") (pintype "bidirectional"))
    )
    (net (code "38") (name "unconnected-(U1-AN6{slash}ERXERR{slash}AETXERR{slash}RB11-Pad35)") (class "Default")
      (node (ref "U1") (pin "35") (pinfunction "AN6/ERXERR/AETXERR/RB11_35") (pintype "bidirectional"))
    )
    (net (code "39") (name "unconnected-(U1-AN8{slash}ERXD1{slash}AECOL{slash}RB13-Pad42)") (class "Default")
      (node (ref "U1") (pin "42") (pinfunction "AN8/ERXD1/AECOL/RB13_42") (pintype "bidirectional"))
    )
    (net (code "40") (name "unconnected-(U1-AN25{slash}AERXD0{slash}RPE8{slash}RE8-Pad18)") (class "Default")
      (node (ref "U1") (pin "18") (pinfunction "AN25/AERXD0/RPE8/RE8_18") (pintype "bidirectional"))
    )
    (net (code "41") (name "unconnected-(U1-AN26{slash}AERXD1{slash}RPE9{slash}RE9-Pad19)") (class "Default")
      (node (ref "U1") (pin "19") (pinfunction "AN26/AERXD1/RPE9/RE9_19") (pintype "bidirectional"))
    )
    (net (code "42") (name "unconnected-(U1-AN32{slash}AETXD0{slash}RPD14{slash}RD14-Pad47)") (class "Default")
      (node (ref "U1") (pin "47") (pinfunction "AN32/AETXD0/RPD14/RD14_47") (pintype "bidirectional"))
    )
    (net (code "43") (name "unconnected-(U1-AN33{slash}AETXD1{slash}RPD15{slash}SCK6{slash}RD15-Pad48)") (class "Default")
      (node (ref "U1") (pin "48") (pinfunction "AN33/AETXD1/RPD15/SCK6/RD15_48") (pintype "bidirectional"))
    )
    (net (code "44") (name "unconnected-(U1-AN45{slash}C1INA{slash}RPB5{slash}RB5-Pad20)") (class "Default")
      (node (ref "U1") (pin "20") (pinfunction "AN45/C1INA/RPB5/RB5_20") (pintype "bidirectional"))
    )
    (net (code "45") (name "unconnected-(U1-EBIA0{slash}AN10{slash}ERXD3{slash}AETXD2{slash}RPB15{slash}OCFB{slash}PMA0{slash}RB15-Pad44)") (class "Default")
      (node (ref "U1") (pin "44") (pinfunction "EBIA0/AN10/ERXD3/AETXD2/RPB15/OCFB/PMA0/RB15_44") (pintype "bidirectional"))
    )
    (net (code "46") (name "unconnected-(U1-EBIA1{slash}AN9{slash}ERXD2{slash}AETXD3{slash}RPB14{slash}SCK3{slash}PMA1{slash}RB14-Pad43)") (class "Default")
      (node (ref "U1") (pin "43") (pinfunction "EBIA1/AN9/ERXD2/AETXD3/RPB14/SCK3/PMA1/RB14_43") (pintype "bidirectional"))
    )
    (net (code "47") (name "unconnected-(U1-EBIA2{slash}AN11{slash}C2INC{slash}ERXCLK{slash}EREFCLK{slash}AERXCLK{slash}AEREFCLK{slash}RPG9{slash}PMA2{slash}RG9-Pad16)") (class "Default")
      (node (ref "U1") (pin "16") (pinfunction "EBIA2/AN11/C2INC/ERXCLK/EREFCLK/AERXCLK/AEREFCLK/RPG9/PMA2/RG9_16") (pintype "bidirectional"))
    )
    (net (code "48") (name "unconnected-(U1-EBIA3{slash}AN12{slash}C2IND{slash}ERXDV{slash}ECRSDV{slash}AERXDV{slash}AECRSDV{slash}RPG8{slash}SCL4{slash}PMA3{slash}RG8-Pad12)") (class "Default")
      (node (ref "U1") (pin "12") (pinfunction "EBIA3/AN12/C2IND/ERXDV/ECRSDV/AERXDV/AECRSDV/RPG8/SCL4/PMA3/RG8_12") (pintype "bidirectional"))
    )
    (net (code "49") (name "unconnected-(U1-EBIA5{slash}AN34{slash}PMA5{slash}RA5-Pad2)") (class "Default")
      (node (ref "U1") (pin "2") (pinfunction "EBIA5/AN34/PMA5/RA5_2") (pintype "bidirectional"))
    )
    (net (code "50") (name "unconnected-(U1-EBIA6{slash}AN22{slash}RPC1{slash}PMA6{slash}RC1-Pad6)") (class "Default")
      (node (ref "U1") (pin "6") (pinfunction "EBIA6/AN22/RPC1/PMA6/RC1_6") (pintype "bidirectional"))
    )
    (net (code "51") (name "unconnected-(U1-EBIA7{slash}AN49{slash}RPB9{slash}PMA7{slash}RB9-Pad33)") (class "Default")
      (node (ref "U1") (pin "33") (pinfunction "EBIA7/AN49/RPB9/PMA7/RB9_33") (pintype "bidirectional"))
    )
    (net (code "52") (name "unconnected-(U1-EBIA8{slash}RPF5{slash}SCL5{slash}PMA8{slash}RF5-Pad65)") (class "Default")
      (node (ref "U1") (pin "65") (pinfunction "EBIA8/RPF5/SCL5/PMA8/RF5_65") (pintype "bidirectional"))
    )
    (net (code "53") (name "unconnected-(U1-EBIA9{slash}RPF4{slash}SDA5{slash}PMA9{slash}RF4-Pad64)") (class "Default")
      (node (ref "U1") (pin "64") (pinfunction "EBIA9/RPF4/SDA5/PMA9/RF4_64") (pintype "bidirectional"))
    )
    (net (code "54") (name "unconnected-(U1-EBIA10{slash}AN48{slash}RPB8{slash}PMA10{slash}RB8-Pad32)") (class "Default")
      (node (ref "U1") (pin "32") (pinfunction "EBIA10/AN48/RPB8/PMA10/RB8_32") (pintype "bidirectional"))
    )
    (net (code "55") (name "unconnected-(U1-EBIA14{slash}PMCS1{slash}PMA14{slash}RA4-Pad61)") (class "Default")
      (node (ref "U1") (pin "61") (pinfunction "EBIA14/PMCS1/PMA14/RA4_61") (pintype "bidirectional"))
    )
    (net (code "56") (name "unconnected-(U1-EBIA15{slash}RPD9{slash}PMCS2{slash}PMA15{slash}RD9-Pad68)") (class "Default")
      (node (ref "U1") (pin "68") (pinfunction "EBIA15/RPD9/PMCS2/PMA15/RD9_68") (pintype "bidirectional"))
    )
    (net (code "57") (name "unconnected-(U1-EBID0{slash}PMD0{slash}RE0-Pad91)") (class "Default")
      (node (ref "U1") (pin "91") (pinfunction "EBID0/PMD0/RE0_91") (pintype "bidirectional"))
    )
    (net (code "58") (name "unconnected-(U1-EBID1{slash}PMD1{slash}RE1-Pad94)") (class "Default")
      (node (ref "U1") (pin "94") (pinfunction "EBID1/PMD1/RE1_94") (pintype "bidirectional"))
    )
    (net (code "59") (name "unconnected-(U1-EBID2{slash}PMD2{slash}RE2-Pad98)") (class "Default")
      (node (ref "U1") (pin "98") (pinfunction "EBID2/PMD2/RE2_98") (pintype "bidirectional"))
    )
    (net (code "60") (name "unconnected-(U1-EBID3{slash}RPE3{slash}PMD3{slash}RE3-Pad99)") (class "Default")
      (node (ref "U1") (pin "99") (pinfunction "EBID3/RPE3/PMD3/RE3_99") (pintype "bidirectional"))
    )
    (net (code "61") (name "unconnected-(U1-EBID4{slash}AN18{slash}PMD4{slash}RE4-Pad100)") (class "Default")
      (node (ref "U1") (pin "100") (pinfunction "EBID4/AN18/PMD4/RE4_100") (pintype "bidirectional"))
    )
    (net (code "62") (name "unconnected-(U1-EBID5{slash}AN17{slash}RPE5{slash}PMD5{slash}RE5-Pad3)") (class "Default")
      (node (ref "U1") (pin "3") (pinfunction "EBID5/AN17/RPE5/PMD5/RE5_3") (pintype "bidirectional"))
    )
    (net (code "63") (name "unconnected-(U1-EBID6{slash}AN16{slash}PMD6{slash}RE6-Pad4)") (class "Default")
      (node (ref "U1") (pin "4") (pinfunction "EBID6/AN16/PMD6/RE6_4") (pintype "bidirectional"))
    )
    (net (code "64") (name "unconnected-(U1-EBID7{slash}AN15{slash}PMD7{slash}RE7-Pad5)") (class "Default")
      (node (ref "U1") (pin "5") (pinfunction "EBID7/AN15/PMD7/RE7_5") (pintype "bidirectional"))
    )
    (net (code "65") (name "unconnected-(U1-EBID8{slash}RPG0{slash}PMD8{slash}RG0-Pad88)") (class "Default")
      (node (ref "U1") (pin "88") (pinfunction "EBID8/RPG0/PMD8/RG0_88") (pintype "bidirectional"))
    )
    (net (code "66") (name "unconnected-(U1-EBID9{slash}ETXERR{slash}RPG1{slash}PMD9{slash}RG1-Pad87)") (class "Default")
      (node (ref "U1") (pin "87") (pinfunction "EBID9/ETXERR/RPG1/PMD9/RG1_87") (pintype "bidirectional"))
    )
    (net (code "67") (name "unconnected-(U1-EBID10{slash}ETXD0{slash}RPF1{slash}PMD10{slash}RF1-Pad86)") (class "Default")
      (node (ref "U1") (pin "86") (pinfunction "EBID10/ETXD0/RPF1/PMD10/RF1_86") (pintype "bidirectional"))
    )
    (net (code "68") (name "unconnected-(U1-EBID11{slash}ETXD1{slash}RPF0{slash}PMD11{slash}RF0-Pad85)") (class "Default")
      (node (ref "U1") (pin "85") (pinfunction "EBID11/ETXD1/RPF0/PMD11/RF0_85") (pintype "bidirectional"))
    )
    (net (code "69") (name "unconnected-(U1-EBID12{slash}ETXD2{slash}RPD12{slash}PMD12{slash}RD12-Pad79)") (class "Default")
      (node (ref "U1") (pin "79") (pinfunction "EBID12/ETXD2/RPD12/PMD12/RD12_79") (pintype "bidirectional"))
    )
    (net (code "70") (name "unconnected-(U1-EBID13{slash}ETXD3{slash}PMD13{slash}RD13-Pad80)") (class "Default")
      (node (ref "U1") (pin "80") (pinfunction "EBID13/ETXD3/PMD13/RD13_80") (pintype "bidirectional"))
    )
    (net (code "71") (name "unconnected-(U1-EBID14{slash}ETXEN{slash}RPD2{slash}PMD14{slash}RD2-Pad77)") (class "Default")
      (node (ref "U1") (pin "77") (pinfunction "EBID14/ETXEN/RPD2/PMD14/RD2_77") (pintype "bidirectional"))
    )
    (net (code "72") (name "unconnected-(U1-EBID15{slash}ETXCLK{slash}RPD3{slash}PMD15{slash}RD3-Pad78)") (class "Default")
      (node (ref "U1") (pin "78") (pinfunction "EBID15/ETXCLK/RPD3/PMD15/RD3_78") (pintype "bidirectional"))
    )
    (net (code "73") (name "unconnected-(U1-EBIRDY1{slash}SDA2{slash}RA3-Pad60)") (class "Default")
      (node (ref "U1") (pin "60") (pinfunction "EBIRDY1/SDA2/RA3_60") (pintype "bidirectional"))
    )
    (net (code "74") (name "unconnected-(U1-EBIRDY3{slash}RPF2{slash}SDA3{slash}RF2-Pad57)") (class "Default")
      (node (ref "U1") (pin "57") (pinfunction "EBIRDY3/RPF2/SDA3/RF2_57") (pintype "bidirectional"))
    )
    (net (code "75") (name "unconnected-(U1-EMDC{slash}AEMDC{slash}RPD11{slash}RD11-Pad70)") (class "Default")
      (node (ref "U1") (pin "70") (pinfunction "EMDC/AEMDC/RPD11/RD11_70") (pintype "bidirectional"))
    )
    (net (code "76") (name "unconnected-(U1-EMDIO{slash}AEMDIO{slash}RPD0{slash}RTCC{slash}INT0{slash}RD0-Pad71)") (class "Default")
      (node (ref "U1") (pin "71") (pinfunction "EMDIO/AEMDIO/RPD0/RTCC/INT0/RD0_71") (pintype "bidirectional"))
    )
    (net (code "77") (name "unconnected-(U1-OSCI{slash}CLKI{slash}RC12-Pad49)") (class "Default")
      (node (ref "U1") (pin "49") (pinfunction "OSCI/CLKI/RC12_49") (pintype "bidirectional"))
    )
    (net (code "78") (name "unconnected-(U1-OSCO{slash}CLKO{slash}RC15-Pad50)") (class "Default")
      (node (ref "U1") (pin "50") (pinfunction "OSCO/CLKO/RC15_50") (pintype "bidirectional"))
    )
    (net (code "79") (name "unconnected-(U1-PGEC1{slash}AN1{slash}RPB1{slash}RB1-Pad24)") (class "Default")
      (node (ref "U1") (pin "24") (pinfunction "PGEC1/AN1/RPB1/RB1_24") (pintype "bidirectional"))
    )
    (net (code "80") (name "unconnected-(U1-PGED1{slash}AN0{slash}RPB0{slash}RB0-Pad25)") (class "Default")
      (node (ref "U1") (pin "25") (pinfunction "PGED1/AN0/RPB0/RB0_25") (pintype "bidirectional"))
    )
    (net (code "81") (name "unconnected-(U1-RPD1{slash}SCK1{slash}RD1-Pad76)") (class "Default")
      (node (ref "U1") (pin "76") (pinfunction "RPD1/SCK1/RD1_76") (pintype "bidirectional"))
    )
    (net (code "82") (name "unconnected-(U1-RPD10{slash}SCK4{slash}RD10-Pad69)") (class "Default")
      (node (ref "U1") (pin "69") (pinfunction "RPD10/SCK4/RD10_69") (pintype "bidirectional"))
    )
    (net (code "83") (name "unconnected-(U1-SOSCI{slash}RPC13{slash}RC13-Pad72)") (class "Default")
      (node (ref "U1") (pin "72") (pinfunction "SOSCI/RPC13/RC13_72") (pintype "bidirectional"))
    )
    (net (code "84") (name "unconnected-(U1-SOSCO{slash}RPC14{slash}T1CK{slash}RC14-Pad73)") (class "Default")
      (node (ref "U1") (pin "73") (pinfunction "SOSCO/RPC14/T1CK/RC14_73") (pintype "bidirectional"))
    )
    (net (code "85") (name "unconnected-(U1-TCK{slash}EBIA19{slash}AN29{slash}RA1-Pad38)") (class "Default")
      (node (ref "U1") (pin "38") (pinfunction "TCK/EBIA19/AN29/RA1_38") (pintype "bidirectional"))
    )
    (net (code "86") (name "unconnected-(U1-TMS{slash}EBIA16{slash}AN24{slash}RA0-Pad17)") (class "Default")
      (node (ref "U1") (pin "17") (pinfunction "TMS/EBIA16/AN24/RA0_17") (pintype "bidirectional"))
    )
    (net (code "87") (name "unconnected-(U1-TRCLK{slash}SQICLK{slash}RA6-Pad89)") (class "Default")
      (node (ref "U1") (pin "89") (pinfunction "TRCLK/SQICLK/RA6_89") (pintype "bidirectional"))
    )
    (net (code "88") (name "unconnected-(U1-TRD0{slash}SQID0{slash}RG13-Pad97)") (class "Default")
      (node (ref "U1") (pin "97") (pinfunction "TRD0/SQID0/RG13_97") (pintype "bidirectional"))
    )
    (net (code "89") (name "unconnected-(U1-TRD1{slash}SQID1{slash}RG12-Pad96)") (class "Default")
      (node (ref "U1") (pin "96") (pinfunction "TRD1/SQID1/RG12_96") (pintype "bidirectional"))
    )
    (net (code "90") (name "unconnected-(U1-TRD2{slash}SQID2{slash}RG14-Pad95)") (class "Default")
      (node (ref "U1") (pin "95") (pinfunction "TRD2/SQID2/RG14_95") (pintype "bidirectional"))
    )
    (net (code "91") (name "unconnected-(U1-TRD3{slash}SQID3{slash}RA7-Pad90)") (class "Default")
      (node (ref "U1") (pin "90") (pinfunction "TRD3/SQID3/RA7_90") (pintype "bidirectional"))
    )
    (net (code "92") (name "unconnected-(U1-USBID{slash}RPF3{slash}RF3-Pad56)") (class "Default")
      (node (ref "U1") (pin "56") (pinfunction "USBID/RPF3/RF3_56") (pintype "bidirectional"))
    )
    (net (code "93") (name "unconnected-(U1-VREF+{slash}CVREF+{slash}AN28{slash}AERXD3{slash}RA10-Pad29)") (class "Default")
      (node (ref "U1") (pin "29") (pinfunction "VREF+/CVREF+/AN28/AERXD3/RA10_29") (pintype "bidirectional"))
    )
    (net (code "94") (name "unconnected-(U1-VREF-{slash}CVREF-{slash}AN27{slash}AERXD2{slash}RA9-Pad28)") (class "Default")
      (node (ref "U1") (pin "28") (pinfunction "VREF-/CVREF-/AN27/AERXD2/RA9_28") (pintype "bidirectional"))
    )
    (net (code "95") (name "unconnected-(U1-~{EBICS0{slash}SCL2{slash}RA2}-Pad59)") (class "Default")
      (node (ref "U1") (pin "59") (pinfunction "~{EBICS0/SCL2/RA2}_59") (pintype "bidirectional"))
    )
    (net (code "96") (name "unconnected-(U1-~{EBIOE{slash}AN19{slash}RPC4{slash}PMRD{slash}RC4}-Pad9)") (class "Default")
      (node (ref "U1") (pin "9") (pinfunction "~{EBIOE/AN19/RPC4/PMRD/RC4}_9") (pintype "bidirectional"))
    )
    (net (code "97") (name "unconnected-(U1-~{EBIWE{slash}AN20{slash}RPC3{slash}PMWR{slash}RC3}-Pad8)") (class "Default")
      (node (ref "U1") (pin "8") (pinfunction "~{EBIWE/AN20/RPC3/PMWR/RC3}_8") (pintype "bidirectional"))
    )
    (net (code "98") (name "unconnected-(U3-PadGPIO0)") (class "Default")
      (node (ref "U3") (pin "GPIO0") (pinfunction "GPIO0_GPIO0") (pintype "bidirectional"))
    )
    (net (code "99") (name "unconnected-(U3-PadGPIO1)") (class "Default")
      (node (ref "U3") (pin "GPIO1") (pinfunction "GPIO1_GPIO1") (pintype "bidirectional"))
    )
    (net (code "100") (name "unconnected-(U3-PadGPIO2)") (class "Default")
      (node (ref "U3") (pin "GPIO2") (pinfunction "GPIO2_GPIO2") (pintype "bidirectional"))
    )
    (net (code "101") (name "unconnected-(U3-PadGPIO3)") (class "Default")
      (node (ref "U3") (pin "GPIO3") (pinfunction "GPIO3_GPIO3") (pintype "bidirectional"))
    )
    (net (code "102") (name "unconnected-(U3-PadGPIO4)") (class "Default")
      (node (ref "U3") (pin "GPIO4") (pinfunction "GPIO4_GPIO4") (pintype "bidirectional"))
    )
    (net (code "103") (name "unconnected-(U3-PadGPIO5)") (class "Default")
      (node (ref "U3") (pin "GPIO5") (pinfunction "GPIO5_GPIO5") (pintype "bidirectional"))
    )
    (net (code "104") (name "unconnected-(U3-PadGPIO6)") (class "Default")
      (node (ref "U3") (pin "GPIO6") (pinfunction "GPIO6_GPIO6") (pintype "bidirectional"))
    )
    (net (code "105") (name "unconnected-(U3-PadGPIO7)") (class "Default")
      (node (ref "U3") (pin "GPIO7") (pinfunction "GPIO7_GPIO7") (pintype "bidirectional"))
    )
    (net (code "106") (name "unconnected-(U3-PadGPIO8)") (class "Default")
      (node (ref "U3") (pin "GPIO8") (pinfunction "GPIO8_GPIO8") (pintype "bidirectional"))
    )
    (net (code "107") (name "unconnected-(U3-PadGPIO9)") (class "Default")
      (node (ref "U3") (pin "GPIO9") (pinfunction "GPIO9_GPIO9") (pintype "bidirectional"))
    )
    (net (code "108") (name "unconnected-(U3-PadGPIO10)") (class "Default")
      (node (ref "U3") (pin "GPIO10") (pinfunction "GPIO10_GPIO10") (pintype "bidirectional"))
    )
    (net (code "109") (name "unconnected-(U3-PadGPIO11)") (class "Default")
      (node (ref "U3") (pin "GPIO11") (pinfunction "GPIO11_GPIO11") (pintype "bidirectional"))
    )
    (net (code "110") (name "unconnected-(U3-PadGPIO12)") (class "Default")
      (node (ref "U3") (pin "GPIO12") (pinfunction "GPIO12_GPIO12") (pintype "bidirectional"))
    )
    (net (code "111") (name "unconnected-(U3-PadGPIO13)") (class "Default")
      (node (ref "U3") (pin "GPIO13") (pinfunction "GPIO13_GPIO13") (pintype "bidirectional"))
    )
    (net (code "112") (name "unconnected-(U3-PadRFL)") (class "Default")
      (node (ref "U3") (pin "RFL") (pinfunction "RFL_RFL") (pintype "bidirectional"))
    )
    (net (code "113") (name "unconnected-(U3-PadUART_CTS)") (class "Default")
      (node (ref "U3") (pin "UART_CTS") (pinfunction "UART_CTS_UART_CTS") (pintype "bidirectional"))
    )
    (net (code "114") (name "unconnected-(U3-PadUART_RTS)") (class "Default")
      (node (ref "U3") (pin "UART_RTS") (pinfunction "UART_RTS_UART_RTS") (pintype "bidirectional"))
    )
    (net (code "115") (name "unconnected-(USB1-ID-Pad4)") (class "Default")
      (node (ref "USB1") (pin "4") (pinfunction "ID_4") (pintype "bidirectional"))
    )
  )
)
